# SnakeSchematic.net
KiCad netlist of a schematic drawn in EAGLE
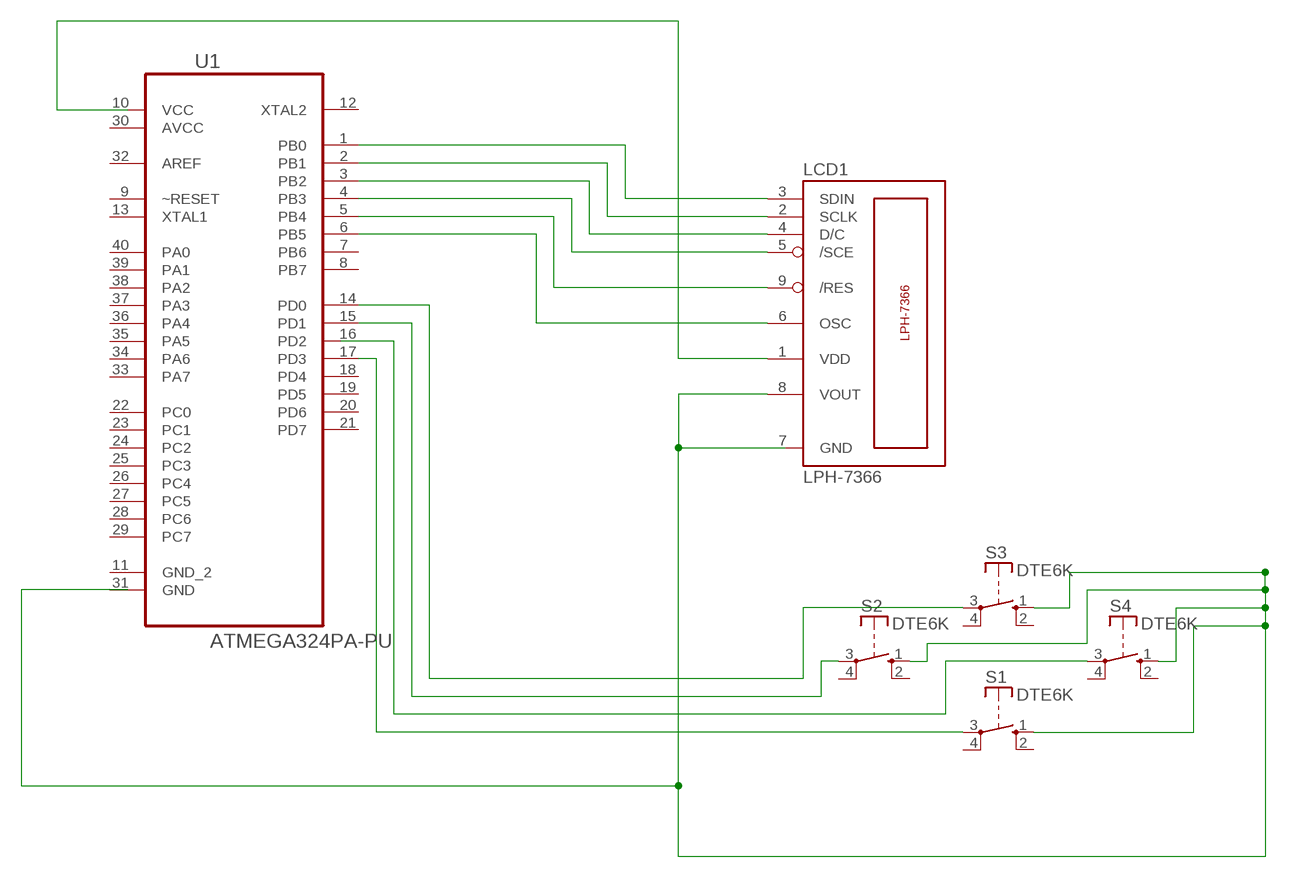
[diagram p0: schematic, sheet 1]

(export (version "E")
  (design (tool "Eeschema 10.0.6"))
  (components
    (comp (ref "LCD1")
      (value "LPH-7366")
      (footprint "eagle-import:LPH-7366")
      (libsource (lib "eagle-import") (part "LPH-7366"))
    )
    (comp (ref "S1")
      (value "DTE6K")
      (footprint "eagle-import:DTE6K")
      (libsource (lib "eagle-import") (part "DTE6K"))
    )
    (comp (ref "S2")
      (value "DTE6K")
      (footprint "eagle-import:DTE6K")
      (libsource (lib "eagle-import") (part "DTE6K"))
    )
    (comp (ref "S3")
      (value "DTE6K")
      (footprint "eagle-import:DTE6K")
      (libsource (lib "eagle-import") (part "DTE6K"))
    )
    (comp (ref "S4")
      (value "DTE6K")
      (footprint "eagle-import:DTE6K")
      (libsource (lib "eagle-import") (part "DTE6K"))
    )
    (comp (ref "U1")
      (value "ATMEGA324PA-PU")
      (footprint "eagle-import:DIP254P1524X482-40")
      (libsource (lib "eagle-import") (part "ATMEGA324PA-PU"))
    )
  )
  (nets
    (net (code "1") (name "/AVCC") (class "Default")
      (node (ref "U1") (pin "30") (pinfunction "AVCC_30") (pintype "power_in"))
    )
    (net (code "2") (name "/GND") (class "Default")
      (node (ref "LCD1") (pin "7") (pinfunction "GND_7") (pintype "power_in"))
    )
    (net (code "3") (name "/VCC") (class "Default")
      (node (ref "U1") (pin "10") (pinfunction "VCC_10") (pintype "power_in"))
    )
    (net (code "4") (name "Net-(LCD1-D{slash}C)") (class "Default")
      (node (ref "LCD1") (pin "4") (pinfunction "D/C_4") (pintype "input"))
      (node (ref "U1") (pin "3") (pinfunction "PB2_3") (pintype "bidirectional"))
    )
    (net (code "5") (name "Net-(LCD1-OSC)") (class "Default")
      (node (ref "LCD1") (pin "6") (pinfunction "OSC_6") (pintype "passive"))
      (node (ref "U1") (pin "6") (pinfunction "PB5_6") (pintype "bidirectional"))
    )
    (net (code "6") (name "Net-(LCD1-SCLK)") (class "Default")
      (node (ref "LCD1") (pin "2") (pinfunction "SCLK_2") (pintype "input"))
      (node (ref "U1") (pin "2") (pinfunction "PB1_2") (pintype "bidirectional"))
    )
    (net (code "7") (name "Net-(LCD1-SDIN)") (class "Default")
      (node (ref "LCD1") (pin "3") (pinfunction "SDIN_3") (pintype "input"))
      (node (ref "U1") (pin "1") (pinfunction "PB0_1") (pintype "bidirectional"))
    )
    (net (code "8") (name "Net-(LCD1-VOUT)") (class "Default")
      (node (ref "LCD1") (pin "8") (pinfunction "VOUT_8") (pintype "passive"))
      (node (ref "S1") (pin "1") (pinfunction "S_1") (pintype "passive"))
      (node (ref "S2") (pin "1") (pinfunction "S_1") (pintype "passive"))
      (node (ref "S3") (pin "1") (pinfunction "S_1") (pintype "passive"))
      (node (ref "S4") (pin "1") (pinfunction "S_1") (pintype "passive"))
    )
    (net (code "9") (name "Net-(LCD1-{slash}RES)") (class "Default")
      (node (ref "LCD1") (pin "9") (pinfunction "/RES_9") (pintype "input"))
      (node (ref "U1") (pin "5") (pinfunction "PB4_5") (pintype "bidirectional"))
    )
    (net (code "10") (name "Net-(LCD1-{slash}SCE)") (class "Default")
      (node (ref "LCD1") (pin "5") (pinfunction "/SCE_5") (pintype "input"))
      (node (ref "U1") (pin "4") (pinfunction "PB3_4") (pintype "bidirectional"))
    )
    (net (code "11") (name "Net-(U1-PD0)") (class "Default")
      (node (ref "S3") (pin "3") (pinfunction "P_3") (pintype "passive"))
      (node (ref "U1") (pin "14") (pinfunction "PD0_14") (pintype "bidirectional"))
    )
    (net (code "12") (name "Net-(U1-PD1)") (class "Default")
      (node (ref "S2") (pin "3") (pinfunction "P_3") (pintype "passive"))
      (node (ref "U1") (pin "15") (pinfunction "PD1_15") (pintype "bidirectional"))
    )
    (net (code "13") (name "Net-(U1-PD3)") (class "Default")
      (node (ref "S1") (pin "3") (pinfunction "P_3") (pintype "passive"))
      (node (ref "U1") (pin "17") (pinfunction "PD3_17") (pintype "bidirectional"))
    )
    (net (code "14") (name "unconnected-(LCD1-VDD-Pad1)") (class "Default")
      (node (ref "LCD1") (pin "1") (pinfunction "VDD_1") (pintype "power_in"))
    )
    (net (code "15") (name "unconnected-(S1-P-Pad4)") (class "Default")
      (node (ref "S1") (pin "4") (pinfunction "P_4") (pintype "passive"))
    )
    (net (code "16") (name "unconnected-(S1-S-Pad2)") (class "Default")
      (node (ref "S1") (pin "2") (pinfunction "S_2") (pintype "passive"))
    )
    (net (code "17") (name "unconnected-(S2-P-Pad4)") (class "Default")
      (node (ref "S2") (pin "4") (pinfunction "P_4") (pintype "passive"))
    )
    (net (code "18") (name "unconnected-(S2-S-Pad2)") (class "Default")
      (node (ref "S2") (pin "2") (pinfunction "S_2") (pintype "passive"))
    )
    (net (code "19") (name "unconnected-(S3-P-Pad4)") (class "Default")
      (node (ref "S3") (pin "4") (pinfunction "P_4") (pintype "passive"))
    )
    (net (code "20") (name "unconnected-(S3-S-Pad2)") (class "Default")
      (node (ref "S3") (pin "2") (pinfunction "S_2") (pintype "passive"))
    )
    (net (code "21") (name "unconnected-(S4-P-Pad3)") (class "Default")
      (node (ref "S4") (pin "3") (pinfunction "P_3") (pintype "passive"))
    )
    (net (code "22") (name "unconnected-(S4-P-Pad4)") (class "Default")
      (node (ref "S4") (pin "4") (pinfunction "P_4") (pintype "passive"))
    )
    (net (code "23") (name "unconnected-(S4-S-Pad2)") (class "Default")
      (node (ref "S4") (pin "2") (pinfunction "S_2") (pintype "passive"))
    )
    (net (code "24") (name "unconnected-(U1-AREF-Pad32)") (class "Default")
      (node (ref "U1") (pin "32") (pinfunction "AREF_32") (pintype "input"))
    )
    (net (code "25") (name "unconnected-(U1-GND-Pad31)") (class "Default")
      (node (ref "U1") (pin "31") (pinfunction "GND_31") (pintype "passive"))
    )
    (net (code "26") (name "unconnected-(U1-GND_2-Pad11)") (class "Default")
      (node (ref "U1") (pin "11") (pinfunction "GND_2_11") (pintype "passive"))
    )
    (net (code "27") (name "unconnected-(U1-PA0-Pad40)") (class "Default")
      (node (ref "U1") (pin "40") (pinfunction "PA0_40") (pintype "bidirectional"))
    )
    (net (code "28") (name "unconnected-(U1-PA1-Pad39)") (class "Default")
      (node (ref "U1") (pin "39") (pinfunction "PA1_39") (pintype "bidirectional"))
    )
    (net (code "29") (name "unconnected-(U1-PA2-Pad38)") (class "Default")
      (node (ref "U1") (pin "38") (pinfunction "PA2_38") (pintype "bidirectional"))
    )
    (net (code "30") (name "unconnected-(U1-PA3-Pad37)") (class "Default")
      (node (ref "U1") (pin "37") (pinfunction "PA3_37") (pintype "bidirectional"))
    )
    (net (code "31") (name "unconnected-(U1-PA4-Pad36)") (class "Default")
      (node (ref "U1") (pin "36") (pinfunction "PA4_36") (pintype "bidirectional"))
    )
    (net (code "32") (name "unconnected-(U1-PA5-Pad35)") (class "Default")
      (node (ref "U1") (pin "35") (pinfunction "PA5_35") (pintype "bidirectional"))
    )
    (net (code "33") (name "unconnected-(U1-PA6-Pad34)") (class "Default")
      (node (ref "U1") (pin "34") (pinfunction "PA6_34") (pintype "bidirectional"))
    )
    (net (code "34") (name "unconnected-(U1-PA7-Pad33)") (class "Default")
      (node (ref "U1") (pin "33") (pinfunction "PA7_33") (pintype "bidirectional"))
    )
    (net (code "35") (name "unconnected-(U1-PB6-Pad7)") (class "Default")
      (node (ref "U1") (pin "7") (pinfunction "PB6_7") (pintype "bidirectional"))
    )
    (net (code "36") (name "unconnected-(U1-PB7-Pad8)") (class "Default")
      (node (ref "U1") (pin "8") (pinfunction "PB7_8") (pintype "bidirectional"))
    )
    (net (code "37") (name "unconnected-(U1-PC0-Pad22)") (class "Default")
      (node (ref "U1") (pin "22") (pinfunction "PC0_22") (pintype "bidirectional"))
    )
    (net (code "38") (name "unconnected-(U1-PC1-Pad23)") (class "Default")
      (node (ref "U1") (pin "23") (pinfunction "PC1_23") (pintype "bidirectional"))
    )
    (net (code "39") (name "unconnected-(U1-PC2-Pad24)") (class "Default")
      (node (ref "U1") (pin "24") (pinfunction "PC2_24") (pintype "bidirectional"))
    )
    (net (code "40") (name "unconnected-(U1-PC3-Pad25)") (class "Default")
      (node (ref "U1") (pin "25") (pinfunction "PC3_25") (pintype "bidirectional"))
    )
    (net (code "41") (name "unconnected-(U1-PC4-Pad26)") (class "Default")
      (node (ref "U1") (pin "26") (pinfunction "PC4_26") (pintype "bidirectional"))
    )
    (net (code "42") (name "unconnected-(U1-PC5-Pad27)") (class "Default")
      (node (ref "U1") (pin "27") (pinfunction "PC5_27") (pintype "bidirectional"))
    )
    (net (code "43") (name "unconnected-(U1-PC6-Pad28)") (class "Default")
      (node (ref "U1") (pin "28") (pinfunction "PC6_28") (pintype "bidirectional"))
    )
    (net (code "44") (name "unconnected-(U1-PC7-Pad29)") (class "Default")
      (node (ref "U1") (pin "29") (pinfunction "PC7_29") (pintype "bidirectional"))
    )
    (net (code "45") (name "unconnected-(U1-PD2-Pad16)") (class "Default")
      (node (ref "U1") (pin "16") (pinfunction "PD2_16") (pintype "bidirectional"))
    )
    (net (code "46") (name "unconnected-(U1-PD4-Pad18)") (class "Default")
      (node (ref "U1") (pin "18") (pinfunction "PD4_18") (pintype "bidirectional"))
    )
    (net (code "47") (name "unconnected-(U1-PD5-Pad19)") (class "Default")
      (node (ref "U1") (pin "19") (pinfunction "PD5_19") (pintype "bidirectional"))
    )
    (net (code "48") (name "unconnected-(U1-PD6-Pad20)") (class "Default")
      (node (ref "U1") (pin "20") (pinfunction "PD6_20") (pintype "bidirectional"))
    )
    (net (code "49") (name "unconnected-(U1-PD7-Pad21)") (class "Default")
      (node (ref "U1") (pin "21") (pinfunction "PD7_21") (pintype "bidirectional"))
    )
    (net (code "50") (name "unconnected-(U1-XTAL1-Pad13)") (class "Default")
      (node (ref "U1") (pin "13") (pinfunction "XTAL1_13") (pintype "input"))
    )
    (net (code "51") (name "unconnected-(U1-XTAL2-Pad12)") (class "Default")
      (node (ref "U1") (pin "12") (pinfunction "XTAL2_12") (pintype "output"))
    )
    (net (code "52") (name "unconnected-(U1-~{RESET}-Pad9)") (class "Default")
      (node (ref "U1") (pin "9") (pinfunction "~{RESET}_9") (pintype "input"))
    )
  )
)
